# AS5040_forMotor.net
KiCad netlist of a schematic drawn in EAGLE
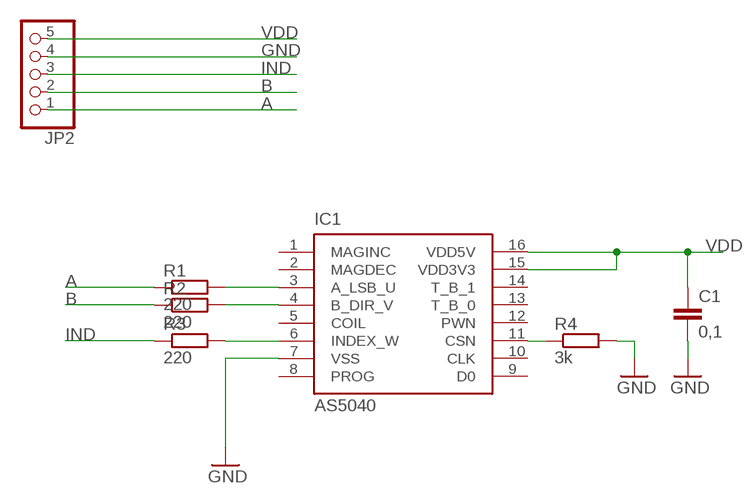
[diagram p0: schematic, sheet 1]

(export (version "E")
  (design (tool "Eeschema 10.0.6"))
  (components
    (comp (ref "C1")
      (value "0,1")
      (footprint "eagle-import:C0805")
      (libsource (lib "eagle-import") (part "C-EUC0805"))
    )
    (comp (ref "IC1")
      (value "AS5040")
      (footprint "eagle-import:SSOP16")
      (fields (field (name "MPN") "AS5040ASSU"))
      (libsource (lib "eagle-import") (part "AS5040"))
    )
    (comp (ref "JP2")
      (value "PINHD-1X5")
      (footprint "eagle-import:1X05")
      (libsource (lib "eagle-import") (part "PINHD-1X5"))
    )
    (comp (ref "R1")
      (value "220")
      (footprint "eagle-import:M0805")
      (libsource (lib "eagle-import") (part "R-EU_M0805"))
    )
    (comp (ref "R2")
      (value "220")
      (footprint "eagle-import:M0805")
      (libsource (lib "eagle-import") (part "R-EU_M0805"))
    )
    (comp (ref "R3")
      (value "220")
      (footprint "eagle-import:M0805")
      (libsource (lib "eagle-import") (part "R-EU_M0805"))
    )
    (comp (ref "R4")
      (value "3k")
      (footprint "eagle-import:M0805")
      (libsource (lib "eagle-import") (part "R-EU_M0805"))
    )
  )
  (nets
    (net (code "1") (name "/A") (class "Default")
      (node (ref "JP2") (pin "1") (pinfunction "1_1") (pintype "passive"))
      (node (ref "R1") (pin "1") (pinfunction "1_1") (pintype "passive"))
    )
    (net (code "2") (name "/B") (class "Default")
      (node (ref "JP2") (pin "2") (pinfunction "2_2") (pintype "passive"))
      (node (ref "R2") (pin "1") (pinfunction "1_1") (pintype "passive"))
    )
    (net (code "3") (name "/IND") (class "Default")
      (node (ref "JP2") (pin "3") (pinfunction "3_3") (pintype "passive"))
      (node (ref "R3") (pin "1") (pinfunction "1_1") (pintype "passive"))
    )
    (net (code "4") (name "/VDD") (class "Default")
      (node (ref "C1") (pin "1") (pinfunction "1_1") (pintype "passive"))
      (node (ref "IC1") (pin "15") (pinfunction "VDD3V3_15") (pintype "passive"))
      (node (ref "IC1") (pin "16") (pinfunction "VDD5V_16") (pintype "passive"))
      (node (ref "JP2") (pin "5") (pinfunction "5_5") (pintype "passive"))
    )
    (net (code "5") (name "GND") (class "Default")
      (node (ref "C1") (pin "2") (pinfunction "2_2") (pintype "passive"))
      (node (ref "IC1") (pin "7") (pinfunction "VSS_7") (pintype "passive"))
      (node (ref "JP2") (pin "4") (pinfunction "4_4") (pintype "passive"))
      (node (ref "R4") (pin "2") (pinfunction "2_2") (pintype "passive"))
    )
    (net (code "6") (name "Net-(IC1-A_LSB_U)") (class "Default")
      (node (ref "IC1") (pin "3") (pinfunction "A_LSB_U_3") (pintype "output"))
      (node (ref "R1") (pin "2") (pinfunction "2_2") (pintype "passive"))
    )
    (net (code "7") (name "Net-(IC1-B_DIR_V)") (class "Default")
      (node (ref "IC1") (pin "4") (pinfunction "B_DIR_V_4") (pintype "output"))
      (node (ref "R2") (pin "2") (pinfunction "2_2") (pintype "passive"))
    )
    (net (code "8") (name "Net-(IC1-CSN)") (class "Default")
      (node (ref "IC1") (pin "11") (pinfunction "CSN_11") (pintype "input"))
      (node (ref "R4") (pin "1") (pinfunction "1_1") (pintype "passive"))
    )
    (net (code "9") (name "Net-(IC1-INDEX_W)") (class "Default")
      (node (ref "IC1") (pin "6") (pinfunction "INDEX_W_6") (pintype "output"))
      (node (ref "R3") (pin "2") (pinfunction "2_2") (pintype "passive"))
    )
    (net (code "10") (name "unconnected-(IC1-CLK-Pad10)") (class "Default")
      (node (ref "IC1") (pin "10") (pinfunction "CLK_10") (pintype "input"))
    )
    (net (code "11") (name "unconnected-(IC1-COIL-Pad5)") (class "Default")
      (node (ref "IC1") (pin "5") (pinfunction "COIL_5") (pintype "no_connect"))
    )
    (net (code "12") (name "unconnected-(IC1-D0-Pad9)") (class "Default")
      (node (ref "IC1") (pin "9") (pinfunction "D0_9") (pintype "tri_state"))
    )
    (net (code "13") (name "unconnected-(IC1-MAGDEC-Pad2)") (class "Default")
      (node (ref "IC1") (pin "2") (pinfunction "MAGDEC_2") (pintype "tri_state"))
    )
    (net (code "14") (name "unconnected-(IC1-MAGINC-Pad1)") (class "Default")
      (node (ref "IC1") (pin "1") (pinfunction "MAGINC_1") (pintype "tri_state"))
    )
    (net (code "15") (name "unconnected-(IC1-PROG-Pad8)") (class "Default")
      (node (ref "IC1") (pin "8") (pinfunction "PROG_8") (pintype "input"))
    )
    (net (code "16") (name "unconnected-(IC1-PWN-Pad12)") (class "Default")
      (node (ref "IC1") (pin "12") (pinfunction "PWN_12") (pintype "passive"))
    )
    (net (code "17") (name "unconnected-(IC1-T_B_0-Pad13)") (class "Default")
      (node (ref "IC1") (pin "13") (pinfunction "T_B_0_13") (pintype "no_connect"))
    )
    (net (code "18") (name "unconnected-(IC1-T_B_1-Pad14)") (class "Default")
      (node (ref "IC1") (pin "14") (pinfunction "T_B_1_14") (pintype "no_connect"))
    )
  )
)
